# PangandaranV1.net
KiCad netlist of a schematic drawn in EAGLE
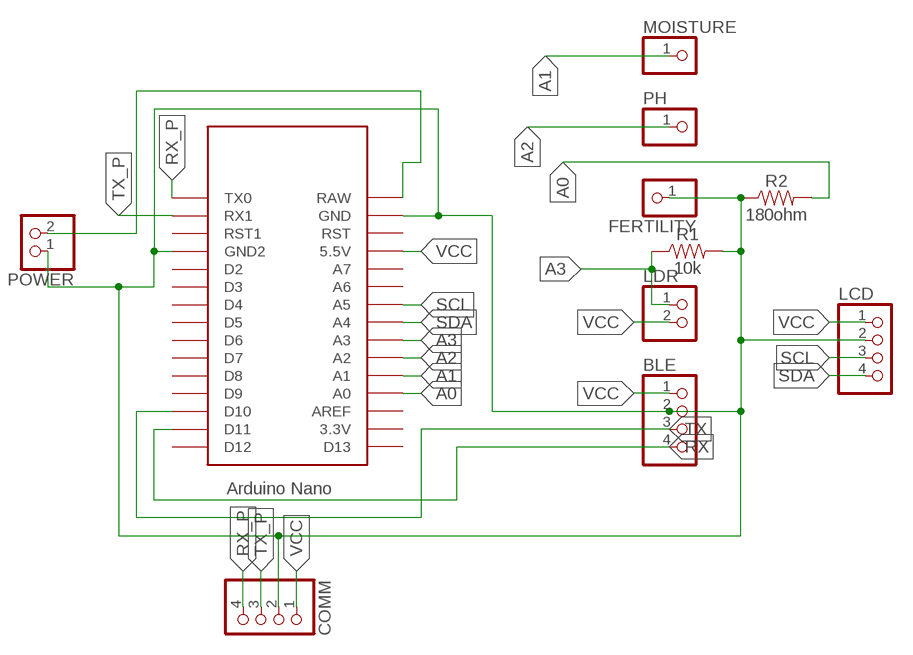
[diagram p0: schematic, sheet 1]

(export (version "E")
  (design (tool "Eeschema 10.0.6"))
  (components
    (comp (ref "BLE")
      (value "PINHD-1X4")
      (footprint "eagle-import:1X04")
      (libsource (lib "eagle-import") (part "PINHD-1X4"))
    )
    (comp (ref "COMM")
      (value "PINHD-1X4")
      (footprint "eagle-import:1X04")
      (libsource (lib "eagle-import") (part "PINHD-1X4"))
    )
    (comp (ref "FERTILITY")
      (value "PINHD-1X1M")
      (footprint "eagle-import:1X01M")
      (libsource (lib "eagle-import") (part "PINHD-1X1M"))
    )
    (comp (ref "LCD")
      (value "PINHD-1X4")
      (footprint "eagle-import:1X04")
      (libsource (lib "eagle-import") (part "PINHD-1X4"))
    )
    (comp (ref "LDR")
      (value "PINHD-1X2")
      (footprint "eagle-import:1X02")
      (libsource (lib "eagle-import") (part "PINHD-1X2"))
    )
    (comp (ref "MOISTURE")
      (value "PINHD-1X1M")
      (footprint "eagle-import:1X01M")
      (libsource (lib "eagle-import") (part "PINHD-1X1M"))
    )
    (comp (ref "PH")
      (value "PINHD-1X1M")
      (footprint "eagle-import:1X01M")
      (libsource (lib "eagle-import") (part "PINHD-1X1M"))
    )
    (comp (ref "POWER")
      (value "PINHD-1X2")
      (footprint "eagle-import:1X02")
      (libsource (lib "eagle-import") (part "PINHD-1X2"))
    )
    (comp (ref "R1")
      (value "10k")
      (footprint "eagle-import:0603")
      (libsource (lib "eagle-import") (part "1KOHM-0603-1/10W-1%"))
    )
    (comp (ref "R2")
      (value "180ohm")
      (footprint "eagle-import:0603")
      (libsource (lib "eagle-import") (part "0OHM-0603-1/10W-5%"))
    )
    (comp (ref "U$2")
      (value "NANO")
      (footprint "eagle-import:NANO")
      (libsource (lib "eagle-import") (part "NANO"))
    )
  )
  (nets
    (net (code "1") (name "A0") (class "Default")
      (node (ref "R2") (pin "2") (pinfunction "2_2") (pintype "passive"))
      (node (ref "U$2") (pin "A0") (pinfunction "A0_A0") (pintype "bidirectional"))
    )
    (net (code "2") (name "A1") (class "Default")
      (node (ref "MOISTURE") (pin "1") (pinfunction "1_1") (pintype "passive"))
      (node (ref "U$2") (pin "A1") (pinfunction "A1_A1") (pintype "bidirectional"))
    )
    (net (code "3") (name "A2") (class "Default")
      (node (ref "PH") (pin "1") (pinfunction "1_1") (pintype "passive"))
      (node (ref "U$2") (pin "A2") (pinfunction "A2_A2") (pintype "bidirectional"))
    )
    (net (code "4") (name "A3") (class "Default")
      (node (ref "LDR") (pin "1") (pinfunction "1_1") (pintype "passive"))
      (node (ref "R1") (pin "1") (pinfunction "1_1") (pintype "passive"))
      (node (ref "U$2") (pin "A3") (pinfunction "A3_A3") (pintype "bidirectional"))
    )
    (net (code "5") (name "Net-(U$2-GND2)") (class "Default")
      (node (ref "BLE") (pin "2") (pinfunction "2_2") (pintype "passive"))
      (node (ref "COMM") (pin "2") (pinfunction "2_2") (pintype "passive"))
      (node (ref "FERTILITY") (pin "1") (pinfunction "1_1") (pintype "passive"))
      (node (ref "LCD") (pin "2") (pinfunction "2_2") (pintype "passive"))
      (node (ref "POWER") (pin "1") (pinfunction "1_1") (pintype "passive"))
      (node (ref "R1") (pin "2") (pinfunction "2_2") (pintype "passive"))
      (node (ref "R2") (pin "1") (pinfunction "1_1") (pintype "passive"))
      (node (ref "U$2") (pin "GND") (pinfunction "GND_GND") (pintype "bidirectional"))
      (node (ref "U$2") (pin "GND1") (pinfunction "GND2_GND1") (pintype "bidirectional"))
    )
    (net (code "6") (name "RX") (class "Default")
      (node (ref "BLE") (pin "4") (pinfunction "4_4") (pintype "passive"))
      (node (ref "U$2") (pin "D11") (pinfunction "D11_D11") (pintype "bidirectional"))
    )
    (net (code "7") (name "RX_P") (class "Default")
      (node (ref "COMM") (pin "4") (pinfunction "4_4") (pintype "passive"))
      (node (ref "U$2") (pin "TX0") (pinfunction "TX0_TX0") (pintype "bidirectional"))
    )
    (net (code "8") (name "SCL") (class "Default")
      (node (ref "LCD") (pin "3") (pinfunction "3_3") (pintype "passive"))
      (node (ref "U$2") (pin "A5") (pinfunction "A5_A5") (pintype "bidirectional"))
    )
    (net (code "9") (name "SDA") (class "Default")
      (node (ref "LCD") (pin "4") (pinfunction "4_4") (pintype "passive"))
      (node (ref "U$2") (pin "A4") (pinfunction "A4_A4") (pintype "bidirectional"))
    )
    (net (code "10") (name "TX") (class "Default")
      (node (ref "BLE") (pin "3") (pinfunction "3_3") (pintype "passive"))
      (node (ref "U$2") (pin "D10") (pinfunction "D10_D10") (pintype "bidirectional"))
    )
    (net (code "11") (name "TX_P") (class "Default")
      (node (ref "COMM") (pin "3") (pinfunction "3_3") (pintype "passive"))
      (node (ref "U$2") (pin "RX1") (pinfunction "RX1_RX1") (pintype "bidirectional"))
    )
    (net (code "12") (name "VCC") (class "Default")
      (node (ref "BLE") (pin "1") (pinfunction "1_1") (pintype "passive"))
      (node (ref "COMM") (pin "1") (pinfunction "1_1") (pintype "passive"))
      (node (ref "LCD") (pin "1") (pinfunction "1_1") (pintype "passive"))
      (node (ref "LDR") (pin "2") (pinfunction "2_2") (pintype "passive"))
      (node (ref "POWER") (pin "2") (pinfunction "2_2") (pintype "passive"))
      (node (ref "U$2") (pin "5V") (pinfunction "5.5V_5V") (pintype "bidirectional"))
      (node (ref "U$2") (pin "RAW") (pinfunction "RAW_RAW") (pintype "bidirectional"))
    )
    (net (code "13") (name "unconnected-(U$2-Pad3.3V)") (class "Default")
      (node (ref "U$2") (pin "3.3V") (pinfunction "3.3V_3.3V") (pintype "bidirectional"))
    )
    (net (code "14") (name "unconnected-(U$2-PadA6)") (class "Default")
      (node (ref "U$2") (pin "A6") (pinfunction "A6_A6") (pintype "bidirectional"))
    )
    (net (code "15") (name "unconnected-(U$2-PadA7)") (class "Default")
      (node (ref "U$2") (pin "A7") (pinfunction "A7_A7") (pintype "bidirectional"))
    )
    (net (code "16") (name "unconnected-(U$2-PadAREF)") (class "Default")
      (node (ref "U$2") (pin "AREF") (pinfunction "AREF_AREF") (pintype "bidirectional"))
    )
    (net (code "17") (name "unconnected-(U$2-PadD2)") (class "Default")
      (node (ref "U$2") (pin "D2") (pinfunction "D2_D2") (pintype "bidirectional"))
    )
    (net (code "18") (name "unconnected-(U$2-PadD3)") (class "Default")
      (node (ref "U$2") (pin "D3") (pinfunction "D3_D3") (pintype "bidirectional"))
    )
    (net (code "19") (name "unconnected-(U$2-PadD4)") (class "Default")
      (node (ref "U$2") (pin "D4") (pinfunction "D4_D4") (pintype "bidirectional"))
    )
    (net (code "20") (name "unconnected-(U$2-PadD5)") (class "Default")
      (node (ref "U$2") (pin "D5") (pinfunction "D5_D5") (pintype "bidirectional"))
    )
    (net (code "21") (name "unconnected-(U$2-PadD6)") (class "Default")
      (node (ref "U$2") (pin "D6") (pinfunction "D6_D6") (pintype "bidirectional"))
    )
    (net (code "22") (name "unconnected-(U$2-PadD7)") (class "Default")
      (node (ref "U$2") (pin "D7") (pinfunction "D7_D7") (pintype "bidirectional"))
    )
    (net (code "23") (name "unconnected-(U$2-PadD8)") (class "Default")
      (node (ref "U$2") (pin "D8") (pinfunction "D8_D8") (pintype "bidirectional"))
    )
    (net (code "24") (name "unconnected-(U$2-PadD9)") (class "Default")
      (node (ref "U$2") (pin "D9") (pinfunction "D9_D9") (pintype "bidirectional"))
    )
    (net (code "25") (name "unconnected-(U$2-PadD12)") (class "Default")
      (node (ref "U$2") (pin "D12") (pinfunction "D12_D12") (pintype "bidirectional"))
    )
    (net (code "26") (name "unconnected-(U$2-PadD13)") (class "Default")
      (node (ref "U$2") (pin "D13") (pinfunction "D13_D13") (pintype "bidirectional"))
    )
    (net (code "27") (name "unconnected-(U$2-PadICSP1)") (class "Default")
      (node (ref "U$2") (pin "ICSP1") (pinfunction "ICSP1_ICSP1") (pintype "bidirectional"))
    )
    (net (code "28") (name "unconnected-(U$2-PadICSP2)") (class "Default")
      (node (ref "U$2") (pin "ICSP2") (pinfunction "ICSP2_ICSP2") (pintype "bidirectional"))
    )
    (net (code "29") (name "unconnected-(U$2-PadICSP3)") (class "Default")
      (node (ref "U$2") (pin "ICSP3") (pinfunction "ICSP3_ICSP3") (pintype "bidirectional"))
    )
    (net (code "30") (name "unconnected-(U$2-PadICSP4)") (class "Default")
      (node (ref "U$2") (pin "ICSP4") (pinfunction "ICSP4_ICSP4") (pintype "bidirectional"))
    )
    (net (code "31") (name "unconnected-(U$2-PadICSP5)") (class "Default")
      (node (ref "U$2") (pin "ICSP5") (pinfunction "ICSP5_ICSP5") (pintype "bidirectional"))
    )
    (net (code "32") (name "unconnected-(U$2-PadICSP6)") (class "Default")
      (node (ref "U$2") (pin "ICSP6") (pinfunction "ICSP6_ICSP6") (pintype "bidirectional"))
    )
    (net (code "33") (name "unconnected-(U$2-PadRST)") (class "Default")
      (node (ref "U$2") (pin "RST") (pinfunction "RST_RST") (pintype "bidirectional"))
    )
    (net (code "34") (name "unconnected-(U$2-PadRST1)") (class "Default")
      (node (ref "U$2") (pin "RST1") (pinfunction "RST1_RST1") (pintype "bidirectional"))
    )
  )
)
